# led3x3.net
KiCad netlist of a schematic drawn in EAGLE
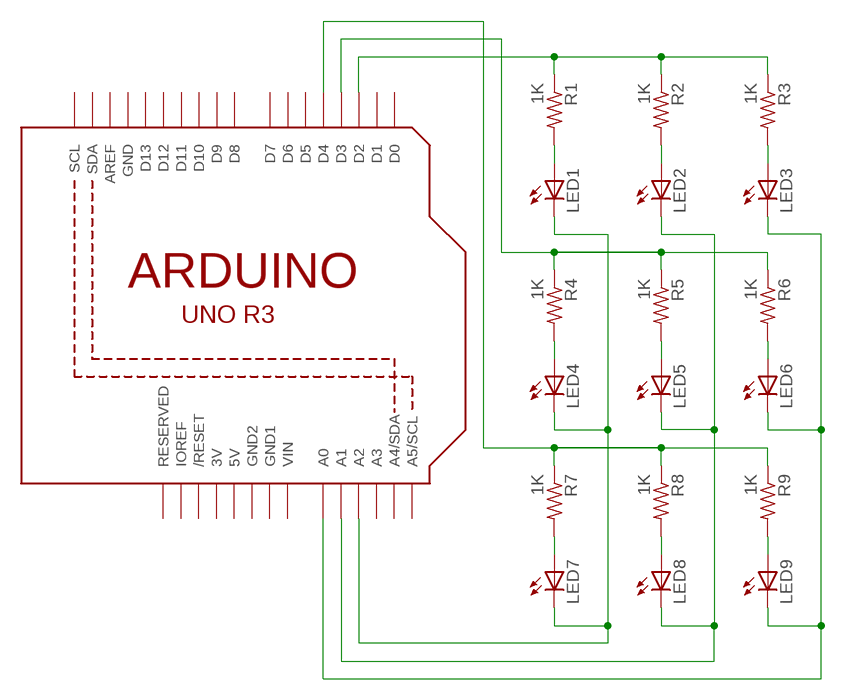
[diagram p0: schematic, sheet 1]

(export (version "E")
  (design (tool "Eeschema 10.0.6"))
  (components
    (comp (ref "LED1")
      (value "LED5MM")
      (footprint "eagle-import:LED5MM")
      (libsource (lib "eagle-import") (part "LED5MM"))
    )
    (comp (ref "LED2")
      (value "LED5MM")
      (footprint "eagle-import:LED5MM")
      (libsource (lib "eagle-import") (part "LED5MM"))
    )
    (comp (ref "LED3")
      (value "LED5MM")
      (footprint "eagle-import:LED5MM")
      (libsource (lib "eagle-import") (part "LED5MM"))
    )
    (comp (ref "LED4")
      (value "LED5MM")
      (footprint "eagle-import:LED5MM")
      (libsource (lib "eagle-import") (part "LED5MM"))
    )
    (comp (ref "LED5")
      (value "LED5MM")
      (footprint "eagle-import:LED5MM")
      (libsource (lib "eagle-import") (part "LED5MM"))
    )
    (comp (ref "LED6")
      (value "LED5MM")
      (footprint "eagle-import:LED5MM")
      (libsource (lib "eagle-import") (part "LED5MM"))
    )
    (comp (ref "LED7")
      (value "LED5MM")
      (footprint "eagle-import:LED5MM")
      (libsource (lib "eagle-import") (part "LED5MM"))
    )
    (comp (ref "LED8")
      (value "LED5MM")
      (footprint "eagle-import:LED5MM")
      (libsource (lib "eagle-import") (part "LED5MM"))
    )
    (comp (ref "LED9")
      (value "LED5MM")
      (footprint "eagle-import:LED5MM")
      (libsource (lib "eagle-import") (part "LED5MM"))
    )
    (comp (ref "R1")
      (value "1K")
      (footprint "eagle-import:0207_10")
      (libsource (lib "eagle-import") (part "R-US_0207/10"))
    )
    (comp (ref "R2")
      (value "1K")
      (footprint "eagle-import:0207_10")
      (libsource (lib "eagle-import") (part "R-US_0207/10"))
    )
    (comp (ref "R3")
      (value "1K")
      (footprint "eagle-import:0207_10")
      (libsource (lib "eagle-import") (part "R-US_0207/10"))
    )
    (comp (ref "R4")
      (value "1K")
      (footprint "eagle-import:0207_10")
      (libsource (lib "eagle-import") (part "R-US_0207/10"))
    )
    (comp (ref "R5")
      (value "1K")
      (footprint "eagle-import:0207_10")
      (libsource (lib "eagle-import") (part "R-US_0207/10"))
    )
    (comp (ref "R6")
      (value "1K")
      (footprint "eagle-import:0207_10")
      (libsource (lib "eagle-import") (part "R-US_0207/10"))
    )
    (comp (ref "R7")
      (value "1K")
      (footprint "eagle-import:0207_10")
      (libsource (lib "eagle-import") (part "R-US_0207/10"))
    )
    (comp (ref "R8")
      (value "1K")
      (footprint "eagle-import:0207_10")
      (libsource (lib "eagle-import") (part "R-US_0207/10"))
    )
    (comp (ref "R9")
      (value "1K")
      (footprint "eagle-import:0207_10")
      (libsource (lib "eagle-import") (part "R-US_0207/10"))
    )
    (comp (ref "U1")
      (value "ARDUINOR3-BPLACE")
      (footprint "eagle-import:ARDUINOR3-BPLACE")
      (libsource (lib "eagle-import") (part "ARDUINOR3-BPLACE"))
    )
  )
  (nets
    (net (code "1") (name "/3V") (class "Default")
      (node (ref "U1") (pin "3V") (pinfunction "3V_3V") (pintype "power_in"))
    )
    (net (code "2") (name "/5V") (class "Default")
      (node (ref "U1") (pin "5V") (pinfunction "5V_5V") (pintype "power_in"))
    )
    (net (code "3") (name "/GND") (class "Default")
      (node (ref "U1") (pin "GND") (pinfunction "GND_GND") (pintype "power_in"))
    )
    (net (code "4") (name "/GND1") (class "Default")
      (node (ref "U1") (pin "GND1") (pinfunction "GND1_GND1") (pintype "power_in"))
    )
    (net (code "5") (name "/GND2") (class "Default")
      (node (ref "U1") (pin "GND2") (pinfunction "GND2_GND2") (pintype "power_in"))
    )
    (net (code "6") (name "/VIN") (class "Default")
      (node (ref "U1") (pin "VIN") (pinfunction "VIN_VIN") (pintype "power_in"))
    )
    (net (code "7") (name "Net-(LED1-C)") (class "Default")
      (node (ref "LED1") (pin "K") (pinfunction "C_K") (pintype "passive"))
      (node (ref "LED4") (pin "K") (pinfunction "C_K") (pintype "passive"))
      (node (ref "LED7") (pin "K") (pinfunction "C_K") (pintype "passive"))
      (node (ref "U1") (pin "A2") (pinfunction "A2_A2") (pintype "bidirectional"))
    )
    (net (code "8") (name "Net-(LED1-PadA)") (class "Default")
      (node (ref "LED1") (pin "A") (pinfunction "A_A") (pintype "passive"))
      (node (ref "R1") (pin "2") (pinfunction "2_2") (pintype "passive"))
    )
    (net (code "9") (name "Net-(LED2-C)") (class "Default")
      (node (ref "LED2") (pin "K") (pinfunction "C_K") (pintype "passive"))
      (node (ref "LED5") (pin "K") (pinfunction "C_K") (pintype "passive"))
      (node (ref "LED8") (pin "K") (pinfunction "C_K") (pintype "passive"))
      (node (ref "U1") (pin "A1") (pinfunction "A1_A1") (pintype "bidirectional"))
    )
    (net (code "10") (name "Net-(LED2-PadA)") (class "Default")
      (node (ref "LED2") (pin "A") (pinfunction "A_A") (pintype "passive"))
      (node (ref "R2") (pin "2") (pinfunction "2_2") (pintype "passive"))
    )
    (net (code "11") (name "Net-(LED3-C)") (class "Default")
      (node (ref "LED3") (pin "K") (pinfunction "C_K") (pintype "passive"))
      (node (ref "LED6") (pin "K") (pinfunction "C_K") (pintype "passive"))
      (node (ref "LED9") (pin "K") (pinfunction "C_K") (pintype "passive"))
      (node (ref "U1") (pin "A0") (pinfunction "A0_A0") (pintype "bidirectional"))
    )
    (net (code "12") (name "Net-(LED3-PadA)") (class "Default")
      (node (ref "LED3") (pin "A") (pinfunction "A_A") (pintype "passive"))
      (node (ref "R3") (pin "2") (pinfunction "2_2") (pintype "passive"))
    )
    (net (code "13") (name "Net-(LED4-PadA)") (class "Default")
      (node (ref "LED4") (pin "A") (pinfunction "A_A") (pintype "passive"))
      (node (ref "R4") (pin "2") (pinfunction "2_2") (pintype "passive"))
    )
    (net (code "14") (name "Net-(LED5-PadA)") (class "Default")
      (node (ref "LED5") (pin "A") (pinfunction "A_A") (pintype "passive"))
      (node (ref "R5") (pin "2") (pinfunction "2_2") (pintype "passive"))
    )
    (net (code "15") (name "Net-(LED6-PadA)") (class "Default")
      (node (ref "LED6") (pin "A") (pinfunction "A_A") (pintype "passive"))
      (node (ref "R6") (pin "2") (pinfunction "2_2") (pintype "passive"))
    )
    (net (code "16") (name "Net-(LED7-PadA)") (class "Default")
      (node (ref "LED7") (pin "A") (pinfunction "A_A") (pintype "passive"))
      (node (ref "R7") (pin "2") (pinfunction "2_2") (pintype "passive"))
    )
    (net (code "17") (name "Net-(LED8-PadA)") (class "Default")
      (node (ref "LED8") (pin "A") (pinfunction "A_A") (pintype "passive"))
      (node (ref "R8") (pin "2") (pinfunction "2_2") (pintype "passive"))
    )
    (net (code "18") (name "Net-(LED9-PadA)") (class "Default")
      (node (ref "LED9") (pin "A") (pinfunction "A_A") (pintype "passive"))
      (node (ref "R9") (pin "2") (pinfunction "2_2") (pintype "passive"))
    )
    (net (code "19") (name "Net-(R1-Pad1)") (class "Default")
      (node (ref "R1") (pin "1") (pinfunction "1_1") (pintype "passive"))
      (node (ref "R2") (pin "1") (pinfunction "1_1") (pintype "passive"))
      (node (ref "R3") (pin "1") (pinfunction "1_1") (pintype "passive"))
      (node (ref "U1") (pin "D2") (pinfunction "D2_D2") (pintype "bidirectional"))
    )
    (net (code "20") (name "Net-(R4-Pad1)") (class "Default")
      (node (ref "R4") (pin "1") (pinfunction "1_1") (pintype "passive"))
      (node (ref "R5") (pin "1") (pinfunction "1_1") (pintype "passive"))
      (node (ref "R6") (pin "1") (pinfunction "1_1") (pintype "passive"))
      (node (ref "U1") (pin "D3") (pinfunction "D3_D3") (pintype "bidirectional"))
    )
    (net (code "21") (name "Net-(R7-Pad1)") (class "Default")
      (node (ref "R7") (pin "1") (pinfunction "1_1") (pintype "passive"))
      (node (ref "R8") (pin "1") (pinfunction "1_1") (pintype "passive"))
      (node (ref "R9") (pin "1") (pinfunction "1_1") (pintype "passive"))
      (node (ref "U1") (pin "D4") (pinfunction "D4_D4") (pintype "bidirectional"))
    )
    (net (code "22") (name "unconnected-(U1-A4{slash}SDA-PadA4)") (class "Default")
      (node (ref "U1") (pin "A4") (pinfunction "A4/SDA_A4") (pintype "bidirectional"))
    )
    (net (code "23") (name "unconnected-(U1-A5{slash}SCL-PadA5)") (class "Default")
      (node (ref "U1") (pin "A5") (pinfunction "A5/SCL_A5") (pintype "bidirectional"))
    )
    (net (code "24") (name "unconnected-(U1-PadA3)") (class "Default")
      (node (ref "U1") (pin "A3") (pinfunction "A3_A3") (pintype "bidirectional"))
    )
    (net (code "25") (name "unconnected-(U1-PadAREF)") (class "Default")
      (node (ref "U1") (pin "AREF") (pinfunction "AREF_AREF") (pintype "bidirectional"))
    )
    (net (code "26") (name "unconnected-(U1-PadD0)") (class "Default")
      (node (ref "U1") (pin "D0") (pinfunction "D0_D0") (pintype "bidirectional"))
    )
    (net (code "27") (name "unconnected-(U1-PadD1)") (class "Default")
      (node (ref "U1") (pin "D1") (pinfunction "D1_D1") (pintype "bidirectional"))
    )
    (net (code "28") (name "unconnected-(U1-PadD5)") (class "Default")
      (node (ref "U1") (pin "D5") (pinfunction "D5_D5") (pintype "bidirectional"))
    )
    (net (code "29") (name "unconnected-(U1-PadD6)") (class "Default")
      (node (ref "U1") (pin "D6") (pinfunction "D6_D6") (pintype "bidirectional"))
    )
    (net (code "30") (name "unconnected-(U1-PadD7)") (class "Default")
      (node (ref "U1") (pin "D7") (pinfunction "D7_D7") (pintype "bidirectional"))
    )
    (net (code "31") (name "unconnected-(U1-PadD8)") (class "Default")
      (node (ref "U1") (pin "D8") (pinfunction "D8_D8") (pintype "bidirectional"))
    )
    (net (code "32") (name "unconnected-(U1-PadD9)") (class "Default")
      (node (ref "U1") (pin "D9") (pinfunction "D9_D9") (pintype "bidirectional"))
    )
    (net (code "33") (name "unconnected-(U1-PadD10)") (class "Default")
      (node (ref "U1") (pin "D10") (pinfunction "D10_D10") (pintype "bidirectional"))
    )
    (net (code "34") (name "unconnected-(U1-PadD11)") (class "Default")
      (node (ref "U1") (pin "D11") (pinfunction "D11_D11") (pintype "bidirectional"))
    )
    (net (code "35") (name "unconnected-(U1-PadD12)") (class "Default")
      (node (ref "U1") (pin "D12") (pinfunction "D12_D12") (pintype "bidirectional"))
    )
    (net (code "36") (name "unconnected-(U1-PadD13)") (class "Default")
      (node (ref "U1") (pin "D13") (pinfunction "D13_D13") (pintype "bidirectional"))
    )
    (net (code "37") (name "unconnected-(U1-PadIOREF)") (class "Default")
      (node (ref "U1") (pin "IOREF") (pinfunction "IOREF_IOREF") (pintype "output"))
    )
    (net (code "38") (name "unconnected-(U1-PadRESERVED)") (class "Default")
      (node (ref "U1") (pin "RESERVED") (pinfunction "RESERVED_RESERVED") (pintype "no_connect"))
    )
    (net (code "39") (name "unconnected-(U1-PadSCL)") (class "Default")
      (node (ref "U1") (pin "SCL") (pinfunction "SCL_SCL") (pintype "bidirectional"))
    )
    (net (code "40") (name "unconnected-(U1-PadSDA)") (class "Default")
      (node (ref "U1") (pin "SDA") (pinfunction "SDA_SDA") (pintype "bidirectional"))
    )
    (net (code "41") (name "unconnected-(U1-{slash}RESET-PadRESET)") (class "Default")
      (node (ref "U1") (pin "RESET") (pinfunction "/RESET_RESET") (pintype "bidirectional"))
    )
  )
)
